# CSR8645.net
KiCad netlist of a schematic drawn in Altium Designer
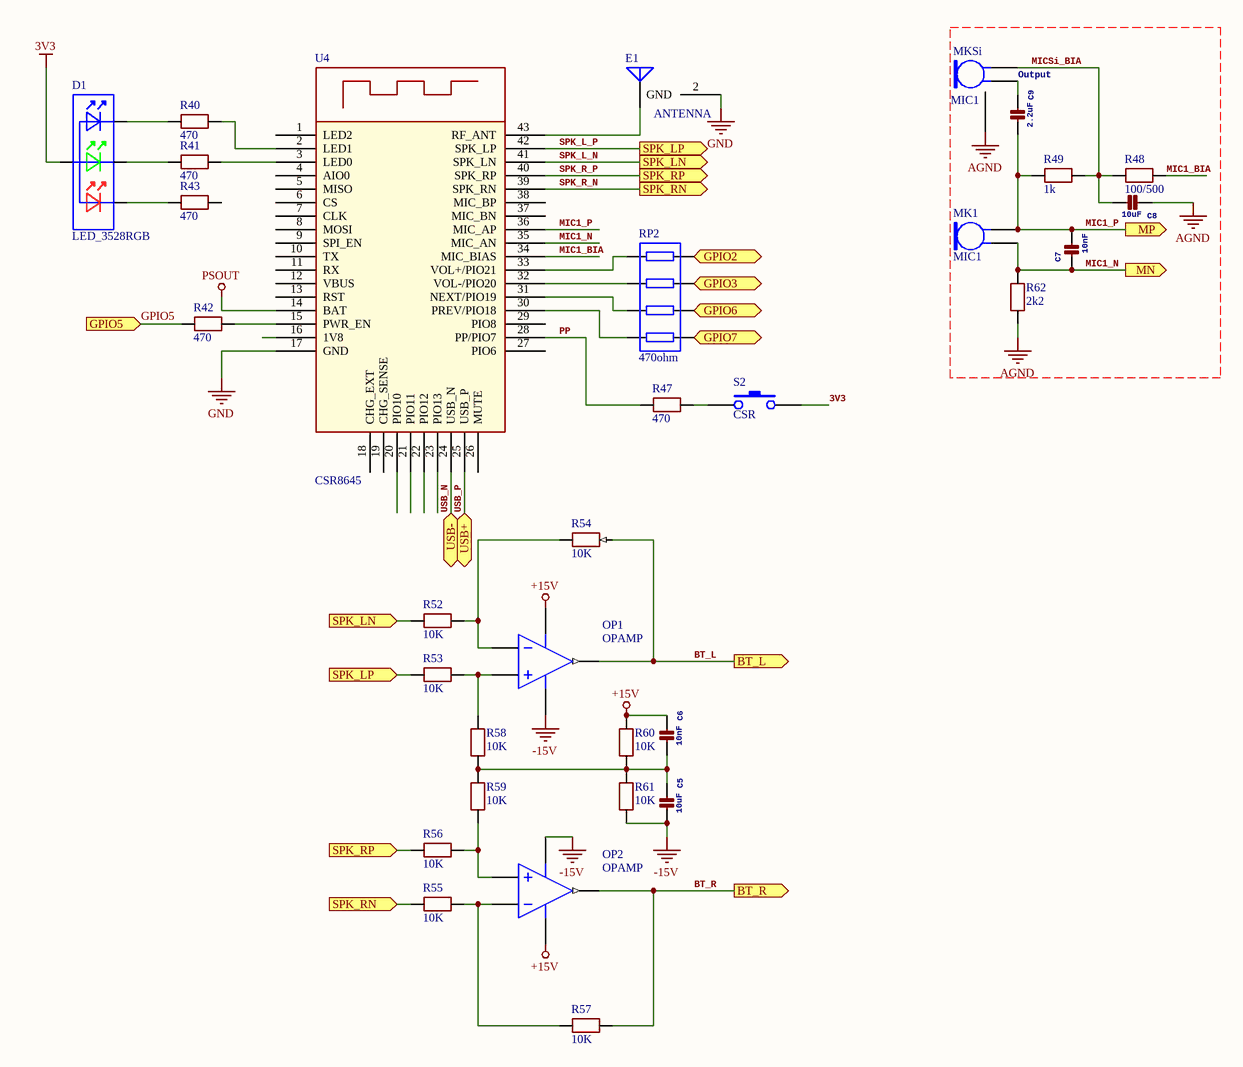
[diagram p0: CSR8645.SchDoc]

(export (version "E")
  (design (tool "Eeschema 10.0.6"))
  (components
    (comp (ref "C5") (value "10uF") (footprint "RB3/7MM") (libsource (lib "9G_SCH") (part "CAP")))
    (comp (ref "C6") (value "10nF") (footprint "WIMA-MKS2C031001A00") (libsource (lib "9G_SCH") (part "CAP")))
    (comp (ref "C7") (value "10nF") (footprint "0201") (libsource (lib "9G_SCH") (part "CAP")))
    (comp (ref "C8") (value "10uF") (footprint "0201") (libsource (lib "") (part "CAP_1")))
    (comp (ref "C9") (value "2.2uF") (footprint "0201") (libsource (lib "9G_SCH") (part "CAP")))
    (comp (ref "D1")
      (value "LED_3528RGB")
      (footprint "1204_RGB")
      (description "LED-3528RGB")
      (libsource (lib "9G_SCH") (part "LED_3528RGB"))
    )
    (comp (ref "E1")
      (value "ANTENNA")
      (footprint "SMA_FR")
      (description "Generic Antenna")
      (libsource (lib "9G_SCH") (part "ANTENNA"))
    )
    (comp (ref "MK1")
      (value "MIC1")
      (footprint "LED-F3")
      (description "Microphone")
      (libsource (lib "9G_SCH") (part "MICROPHONE2"))
    )
    (comp (ref "MKSi")
      (value "MIC1")
      (footprint "ADMP504")
      (description "Microphone")
      (libsource (lib "") (part "MICROPHONE2_1"))
    )
    (comp (ref "OP1")
      (value "OPAMP")
      (footprint "DIP-8")
      (description "Operational Amplifier")
      (libsource (lib "9G_SCH") (part "OPAMP"))
    )
    (comp (ref "OP2")
      (value "OPAMP")
      (footprint "DIP-8")
      (description "Operational Amplifier")
      (libsource (lib "9G_SCH") (part "OPAMP"))
    )
    (comp (ref "R40")
      (value "470")
      (footprint "0603AR")
      (description "Resistor")
      (libsource (lib "9G_SCH") (part "RES2"))
    )
    (comp (ref "R41")
      (value "470")
      (footprint "0603AR")
      (description "Resistor")
      (libsource (lib "9G_SCH") (part "RES2"))
    )
    (comp (ref "R42")
      (value "470")
      (footprint "0603AR")
      (description "Resistor")
      (libsource (lib "9G_SCH") (part "RES2"))
    )
    (comp (ref "R43")
      (value "470")
      (footprint "0603AR")
      (description "Resistor")
      (libsource (lib "9G_SCH") (part "RES2"))
    )
    (comp (ref "R47")
      (value "470")
      (footprint "0603AR")
      (description "Resistor")
      (libsource (lib "9G_SCH") (part "RES2"))
    )
    (comp (ref "R48")
      (value "100/500")
      (footprint "0402")
      (description "Resistor")
      (libsource (lib "9G_SCH") (part "RES2"))
    )
    (comp (ref "R49")
      (value "1k")
      (footprint "0402")
      (description "Resistor")
      (libsource (lib "9G_SCH") (part "RES2"))
    )
    (comp (ref "R52")
      (value "10K")
      (footprint "MELF-R3216-1206")
      (description "Resistor")
      (libsource (lib "9G_SCH") (part "RES2"))
    )
    (comp (ref "R53")
      (value "10K")
      (footprint "MELF-R3216-1206")
      (description "Resistor")
      (libsource (lib "9G_SCH") (part "RES2"))
    )
    (comp (ref "R54")
      (value "10K")
      (footprint "MELF-R3216-1206")
      (description "Resistor")
      (libsource (lib "") (part "RES2_1"))
    )
    (comp (ref "R55")
      (value "10K")
      (footprint "MELF-R3216-1206")
      (description "Resistor")
      (libsource (lib "9G_SCH") (part "RES2"))
    )
    (comp (ref "R56")
      (value "10K")
      (footprint "MELF-R3216-1206")
      (description "Resistor")
      (libsource (lib "9G_SCH") (part "RES2"))
    )
    (comp (ref "R57")
      (value "10K")
      (footprint "MELF-R3216-1206")
      (description "Resistor")
      (libsource (lib "9G_SCH") (part "RES2"))
    )
    (comp (ref "R58")
      (value "10K")
      (footprint "MELF-R3216-1206")
      (description "Resistor")
      (libsource (lib "9G_SCH") (part "RES2"))
    )
    (comp (ref "R59")
      (value "10K")
      (footprint "MELF-R3216-1206")
      (description "Resistor")
      (libsource (lib "9G_SCH") (part "RES2"))
    )
    (comp (ref "R60")
      (value "10K")
      (footprint "MELF-R3216-1206")
      (description "Resistor")
      (libsource (lib "9G_SCH") (part "RES2"))
    )
    (comp (ref "R61")
      (value "10K")
      (footprint "MELF-R3216-1206")
      (description "Resistor")
      (libsource (lib "9G_SCH") (part "RES2"))
    )
    (comp (ref "R62")
      (value "2k2")
      (footprint "0402")
      (description "Resistor")
      (libsource (lib "9G_SCH") (part "RES2"))
    )
    (comp (ref "RP2")
      (value "470ohm")
      (footprint "RN8")
      (description "Resistor Network")
      (libsource (lib "9G_SCH") (part "RESPACK4A"))
    )
    (comp (ref "S2")
      (value "CSR")
      (footprint "sw_side")
      (libsource (lib "Integrated_Library1") (part "SW-PB"))
    )
    (comp (ref "U4")
      (value "CSR8645")
      (footprint "CSR8645")
      (description "Bluetooth Audio")
      (libsource (lib "9G_SCH") (part "CSR8645"))
    )
  )
  (nets
    (net (code "1") (name "+15V") (class "Default")
      (node (ref "C6") (pin "1") (pinfunction "1_1") (pintype "passive"))
      (node (ref "OP1") (pin "7") (pinfunction "V+_7") (pintype "passive"))
      (node (ref "OP2") (pin "7") (pinfunction "V+_7") (pintype "passive"))
      (node (ref "R60") (pin "1") (pinfunction "1_1") (pintype "passive"))
    )
    (net (code "2") (name "-15V") (class "Default")
      (node (ref "C5") (pin "2") (pinfunction "2_2") (pintype "passive"))
      (node (ref "OP1") (pin "4") (pinfunction "V-_4") (pintype "passive"))
      (node (ref "OP2") (pin "4") (pinfunction "V-_4") (pintype "passive"))
      (node (ref "R61") (pin "2") (pinfunction "2_2") (pintype "passive"))
    )
    (net (code "3") (name "/BT_L") (class "Default")
      (node (ref "OP1") (pin "6") (pinfunction "OUT_6") (pintype "output"))
      (node (ref "R54") (pin "1") (pinfunction "1_1") (pintype "input"))
    )
    (net (code "4") (name "/BT_R") (class "Default")
      (node (ref "OP2") (pin "6") (pinfunction "OUT_6") (pintype "output"))
      (node (ref "R57") (pin "1") (pinfunction "1_1") (pintype "passive"))
    )
    (net (code "5") (name "/GPIO2") (class "Default")
      (node (ref "RP2") (pin "8") (pinfunction "8_8") (pintype "passive"))
    )
    (net (code "6") (name "/GPIO3") (class "Default")
      (node (ref "RP2") (pin "7") (pinfunction "7_7") (pintype "passive"))
    )
    (net (code "7") (name "/GPIO5") (class "Default")
      (node (ref "R42") (pin "2") (pinfunction "2_2") (pintype "passive"))
    )
    (net (code "8") (name "/GPIO6") (class "Default")
      (node (ref "RP2") (pin "6") (pinfunction "6_6") (pintype "passive"))
    )
    (net (code "9") (name "/GPIO7") (class "Default")
      (node (ref "RP2") (pin "5") (pinfunction "5_5") (pintype "passive"))
    )
    (net (code "10") (name "/MIC1_BIA") (class "Default")
      (node (ref "R48") (pin "2") (pinfunction "2_2") (pintype "passive"))
      (node (ref "U4") (pin "34") (pinfunction "MIC_BIAS_34") (pintype "passive"))
    )
    (net (code "11") (name "/MIC1_N") (class "Default")
      (node (ref "C7") (pin "2") (pinfunction "2_2") (pintype "passive"))
      (node (ref "MK1") (pin "1") (pinfunction "1_1") (pintype "passive"))
      (node (ref "R62") (pin "1") (pinfunction "1_1") (pintype "passive"))
      (node (ref "U4") (pin "35") (pinfunction "MIC_AN_35") (pintype "passive"))
    )
    (net (code "12") (name "/MIC1_P") (class "Default")
      (node (ref "C7") (pin "1") (pinfunction "1_1") (pintype "passive"))
      (node (ref "C9") (pin "2") (pinfunction "2_2") (pintype "passive"))
      (node (ref "MK1") (pin "2") (pinfunction "2_2") (pintype "passive"))
      (node (ref "R49") (pin "2") (pinfunction "2_2") (pintype "passive"))
      (node (ref "U4") (pin "36") (pinfunction "MIC_AP_36") (pintype "passive"))
    )
    (net (code "13") (name "/MICSi_BIA") (class "Default")
      (node (ref "C8") (pin "2") (pinfunction "2_2") (pintype "passive"))
      (node (ref "MKSi") (pin "3") (pinfunction "VDD_3") (pintype "passive"))
      (node (ref "R48") (pin "1") (pinfunction "1_1") (pintype "passive"))
      (node (ref "R49") (pin "1") (pinfunction "1_1") (pintype "passive"))
    )
    (net (code "14") (name "/PP") (class "Default")
      (node (ref "R47") (pin "2") (pinfunction "2_2") (pintype "passive"))
      (node (ref "U4") (pin "28") (pinfunction "PP/PIO7_28") (pintype "passive"))
    )
    (net (code "15") (name "/SPK_L_N") (class "Default")
      (node (ref "R52") (pin "2") (pinfunction "2_2") (pintype "passive"))
      (node (ref "U4") (pin "41") (pinfunction "SPK_LN_41") (pintype "passive"))
    )
    (net (code "16") (name "/SPK_L_P") (class "Default")
      (node (ref "R53") (pin "2") (pinfunction "2_2") (pintype "passive"))
      (node (ref "U4") (pin "42") (pinfunction "SPK_LP_42") (pintype "passive"))
    )
    (net (code "17") (name "/SPK_R_N") (class "Default")
      (node (ref "R55") (pin "2") (pinfunction "2_2") (pintype "passive"))
      (node (ref "U4") (pin "39") (pinfunction "SPK_RN_39") (pintype "passive"))
    )
    (net (code "18") (name "/SPK_R_P") (class "Default")
      (node (ref "R56") (pin "2") (pinfunction "2_2") (pintype "passive"))
      (node (ref "U4") (pin "40") (pinfunction "SPK_RP_40") (pintype "passive"))
    )
    (net (code "19") (name "/USB_N") (class "Default")
      (node (ref "U4") (pin "24") (pinfunction "USB_N_24") (pintype "passive"))
    )
    (net (code "20") (name "/USB_P") (class "Default")
      (node (ref "U4") (pin "25") (pinfunction "USB_P_25") (pintype "passive"))
    )
    (net (code "21") (name "3V3") (class "Default")
      (node (ref "D1") (pin "1") (pinfunction "+_1") (pintype "passive"))
      (node (ref "S2") (pin "1") (pinfunction "2_1") (pintype "passive"))
    )
    (net (code "22") (name "AGND") (class "Default")
      (node (ref "C8") (pin "1") (pinfunction "1_1") (pintype "passive"))
      (node (ref "MKSi") (pin "2") (pinfunction "GND_2") (pintype "passive"))
      (node (ref "R62") (pin "2") (pinfunction "2_2") (pintype "passive"))
    )
    (net (code "23") (name "GND") (class "Default")
      (node (ref "E1") (pin "2") (pinfunction "GND_2") (pintype "passive"))
      (node (ref "U4") (pin "17") (pinfunction "GND_17") (pintype "passive"))
    )
    (net (code "24") (name "Net-(C5-Pad1)") (class "Default")
      (node (ref "C5") (pin "1") (pinfunction "1_1") (pintype "passive"))
      (node (ref "C6") (pin "2") (pinfunction "2_2") (pintype "passive"))
      (node (ref "R58") (pin "2") (pinfunction "2_2") (pintype "passive"))
      (node (ref "R59") (pin "1") (pinfunction "1_1") (pintype "passive"))
      (node (ref "R60") (pin "2") (pinfunction "2_2") (pintype "passive"))
      (node (ref "R61") (pin "1") (pinfunction "1_1") (pintype "passive"))
    )
    (net (code "25") (name "Net-(D1-B-)") (class "Default")
      (node (ref "D1") (pin "4") (pinfunction "B-_4") (pintype "passive"))
      (node (ref "R40") (pin "2") (pinfunction "2_2") (pintype "passive"))
    )
    (net (code "26") (name "Net-(D1-G-)") (class "Default")
      (node (ref "D1") (pin "3") (pinfunction "G-_3") (pintype "passive"))
      (node (ref "R41") (pin "2") (pinfunction "2_2") (pintype "passive"))
    )
    (net (code "27") (name "Net-(D1-R-)") (class "Default")
      (node (ref "D1") (pin "2") (pinfunction "R-_2") (pintype "passive"))
      (node (ref "R43") (pin "2") (pinfunction "2_2") (pintype "passive"))
    )
    (net (code "28") (name "Net-(E1-A)") (class "Default")
      (node (ref "E1") (pin "1") (pinfunction "A_1") (pintype "passive"))
      (node (ref "U4") (pin "43") (pinfunction "RF_ANT_43") (pintype "passive"))
    )
    (net (code "29") (name "Net-(MKSi-OUTPUT)") (class "Default")
      (node (ref "C9") (pin "1") (pinfunction "1_1") (pintype "passive"))
      (node (ref "MKSi") (pin "1") (pinfunction "OUTPUT_1") (pintype "passive"))
    )
    (net (code "30") (name "Net-(OP1-IN+)") (class "Default")
      (node (ref "OP1") (pin "3") (pinfunction "IN+_3") (pintype "passive"))
      (node (ref "R53") (pin "1") (pinfunction "1_1") (pintype "passive"))
      (node (ref "R58") (pin "1") (pinfunction "1_1") (pintype "passive"))
    )
    (net (code "31") (name "Net-(OP1-IN-)") (class "Default")
      (node (ref "OP1") (pin "2") (pinfunction "IN-_2") (pintype "passive"))
      (node (ref "R52") (pin "1") (pinfunction "1_1") (pintype "passive"))
      (node (ref "R54") (pin "2") (pinfunction "2_2") (pintype "passive"))
    )
    (net (code "32") (name "Net-(OP2-IN+)") (class "Default")
      (node (ref "OP2") (pin "3") (pinfunction "IN+_3") (pintype "passive"))
      (node (ref "R56") (pin "1") (pinfunction "1_1") (pintype "passive"))
      (node (ref "R59") (pin "2") (pinfunction "2_2") (pintype "passive"))
    )
    (net (code "33") (name "Net-(OP2-IN-)") (class "Default")
      (node (ref "OP2") (pin "2") (pinfunction "IN-_2") (pintype "passive"))
      (node (ref "R55") (pin "1") (pinfunction "1_1") (pintype "passive"))
      (node (ref "R57") (pin "2") (pinfunction "2_2") (pintype "passive"))
    )
    (net (code "34") (name "Net-(S2-1)") (class "Default")
      (node (ref "R47") (pin "1") (pinfunction "1_1") (pintype "passive"))
      (node (ref "S2") (pin "2") (pinfunction "1_2") (pintype "passive"))
    )
    (net (code "35") (name "Net-(U4-LED0)") (class "Default")
      (node (ref "R41") (pin "1") (pinfunction "1_1") (pintype "passive"))
      (node (ref "U4") (pin "3") (pinfunction "LED0_3") (pintype "passive"))
    )
    (net (code "36") (name "Net-(U4-LED1)") (class "Default")
      (node (ref "R40") (pin "1") (pinfunction "1_1") (pintype "passive"))
      (node (ref "U4") (pin "2") (pinfunction "LED1_2") (pintype "passive"))
    )
    (net (code "37") (name "Net-(U4-NEXT{slash}PIO19)") (class "Default")
      (node (ref "RP2") (pin "3") (pinfunction "3_3") (pintype "passive"))
      (node (ref "U4") (pin "31") (pinfunction "NEXT/PIO19_31") (pintype "passive"))
    )
    (net (code "38") (name "Net-(U4-PREV{slash}PIO18)") (class "Default")
      (node (ref "RP2") (pin "4") (pinfunction "4_4") (pintype "passive"))
      (node (ref "U4") (pin "30") (pinfunction "PREV/PIO18_30") (pintype "passive"))
    )
    (net (code "39") (name "Net-(U4-PWR_EN)") (class "Default")
      (node (ref "R42") (pin "1") (pinfunction "1_1") (pintype "passive"))
      (node (ref "U4") (pin "15") (pinfunction "PWR_EN_15") (pintype "passive"))
    )
    (net (code "40") (name "Net-(U4-VOL+{slash}PIO21)") (class "Default")
      (node (ref "RP2") (pin "1") (pinfunction "1_1") (pintype "passive"))
      (node (ref "U4") (pin "33") (pinfunction "VOL+/PIO21_33") (pintype "passive"))
    )
    (net (code "41") (name "Net-(U4-VOL-{slash}PIO20)") (class "Default")
      (node (ref "RP2") (pin "2") (pinfunction "2_2") (pintype "passive"))
      (node (ref "U4") (pin "32") (pinfunction "VOL-/PIO20_32") (pintype "passive"))
    )
    (net (code "42") (name "PSOUT") (class "Default")
      (node (ref "U4") (pin "14") (pinfunction "BAT_14") (pintype "passive"))
    )
    (net (code "43") (name "unconnected-(R43-Pad1)") (class "Default")
      (node (ref "R43") (pin "1") (pinfunction "1_1") (pintype "passive"))
    )
    (net (code "44") (name "unconnected-(U4-1V8-Pad16)") (class "Default")
      (node (ref "U4") (pin "16") (pinfunction "1V8_16") (pintype "passive"))
    )
    (net (code "45") (name "unconnected-(U4-AIO0-Pad4)") (class "Default")
      (node (ref "U4") (pin "4") (pinfunction "AIO0_4") (pintype "passive"))
    )
    (net (code "46") (name "unconnected-(U4-CHG_EXT-Pad18)") (class "Default")
      (node (ref "U4") (pin "18") (pinfunction "CHG_EXT_18") (pintype "passive"))
    )
    (net (code "47") (name "unconnected-(U4-CHG_SENSE-Pad19)") (class "Default")
      (node (ref "U4") (pin "19") (pinfunction "CHG_SENSE_19") (pintype "passive"))
    )
    (net (code "48") (name "unconnected-(U4-CLK-Pad7)") (class "Default")
      (node (ref "U4") (pin "7") (pinfunction "CLK_7") (pintype "passive"))
    )
    (net (code "49") (name "unconnected-(U4-CS-Pad6)") (class "Default")
      (node (ref "U4") (pin "6") (pinfunction "CS_6") (pintype "passive"))
    )
    (net (code "50") (name "unconnected-(U4-LED2-Pad1)") (class "Default")
      (node (ref "U4") (pin "1") (pinfunction "LED2_1") (pintype "passive"))
    )
    (net (code "51") (name "unconnected-(U4-MIC_BN-Pad37)") (class "Default")
      (node (ref "U4") (pin "37") (pinfunction "MIC_BN_37") (pintype "passive"))
    )
    (net (code "52") (name "unconnected-(U4-MIC_BP-Pad38)") (class "Default")
      (node (ref "U4") (pin "38") (pinfunction "MIC_BP_38") (pintype "passive"))
    )
    (net (code "53") (name "unconnected-(U4-MISO-Pad5)") (class "Default")
      (node (ref "U4") (pin "5") (pinfunction "MISO_5") (pintype "passive"))
    )
    (net (code "54") (name "unconnected-(U4-MOSI-Pad8)") (class "Default")
      (node (ref "U4") (pin "8") (pinfunction "MOSI_8") (pintype "passive"))
    )
    (net (code "55") (name "unconnected-(U4-MUTE-Pad26)") (class "Default")
      (node (ref "U4") (pin "26") (pinfunction "MUTE_26") (pintype "passive"))
    )
    (net (code "56") (name "unconnected-(U4-PIO6-Pad27)") (class "Default")
      (node (ref "U4") (pin "27") (pinfunction "PIO6_27") (pintype "passive"))
    )
    (net (code "57") (name "unconnected-(U4-PIO8-Pad29)") (class "Default")
      (node (ref "U4") (pin "29") (pinfunction "PIO8_29") (pintype "passive"))
    )
    (net (code "58") (name "unconnected-(U4-PIO10-Pad20)") (class "Default")
      (node (ref "U4") (pin "20") (pinfunction "PIO10_20") (pintype "passive"))
    )
    (net (code "59") (name "unconnected-(U4-PIO11-Pad21)") (class "Default")
      (node (ref "U4") (pin "21") (pinfunction "PIO11_21") (pintype "passive"))
    )
    (net (code "60") (name "unconnected-(U4-PIO12-Pad22)") (class "Default")
      (node (ref "U4") (pin "22") (pinfunction "PIO12_22") (pintype "passive"))
    )
    (net (code "61") (name "unconnected-(U4-PIO13-Pad23)") (class "Default")
      (node (ref "U4") (pin "23") (pinfunction "PIO13_23") (pintype "passive"))
    )
    (net (code "62") (name "unconnected-(U4-RST-Pad13)") (class "Default")
      (node (ref "U4") (pin "13") (pinfunction "RST_13") (pintype "passive"))
    )
    (net (code "63") (name "unconnected-(U4-RX-Pad11)") (class "Default")
      (node (ref "U4") (pin "11") (pinfunction "RX_11") (pintype "passive"))
    )
    (net (code "64") (name "unconnected-(U4-SPI_EN-Pad9)") (class "Default")
      (node (ref "U4") (pin "9") (pinfunction "SPI_EN_9") (pintype "passive"))
    )
    (net (code "65") (name "unconnected-(U4-TX-Pad10)") (class "Default")
      (node (ref "U4") (pin "10") (pinfunction "TX_10") (pintype "passive"))
    )
    (net (code "66") (name "unconnected-(U4-VBUS-Pad12)") (class "Default")
      (node (ref "U4") (pin "12") (pinfunction "VBUS_12") (pintype "passive"))
    )
  )
)
